# mippe_32u4.net
KiCad netlist of a schematic drawn in EAGLE
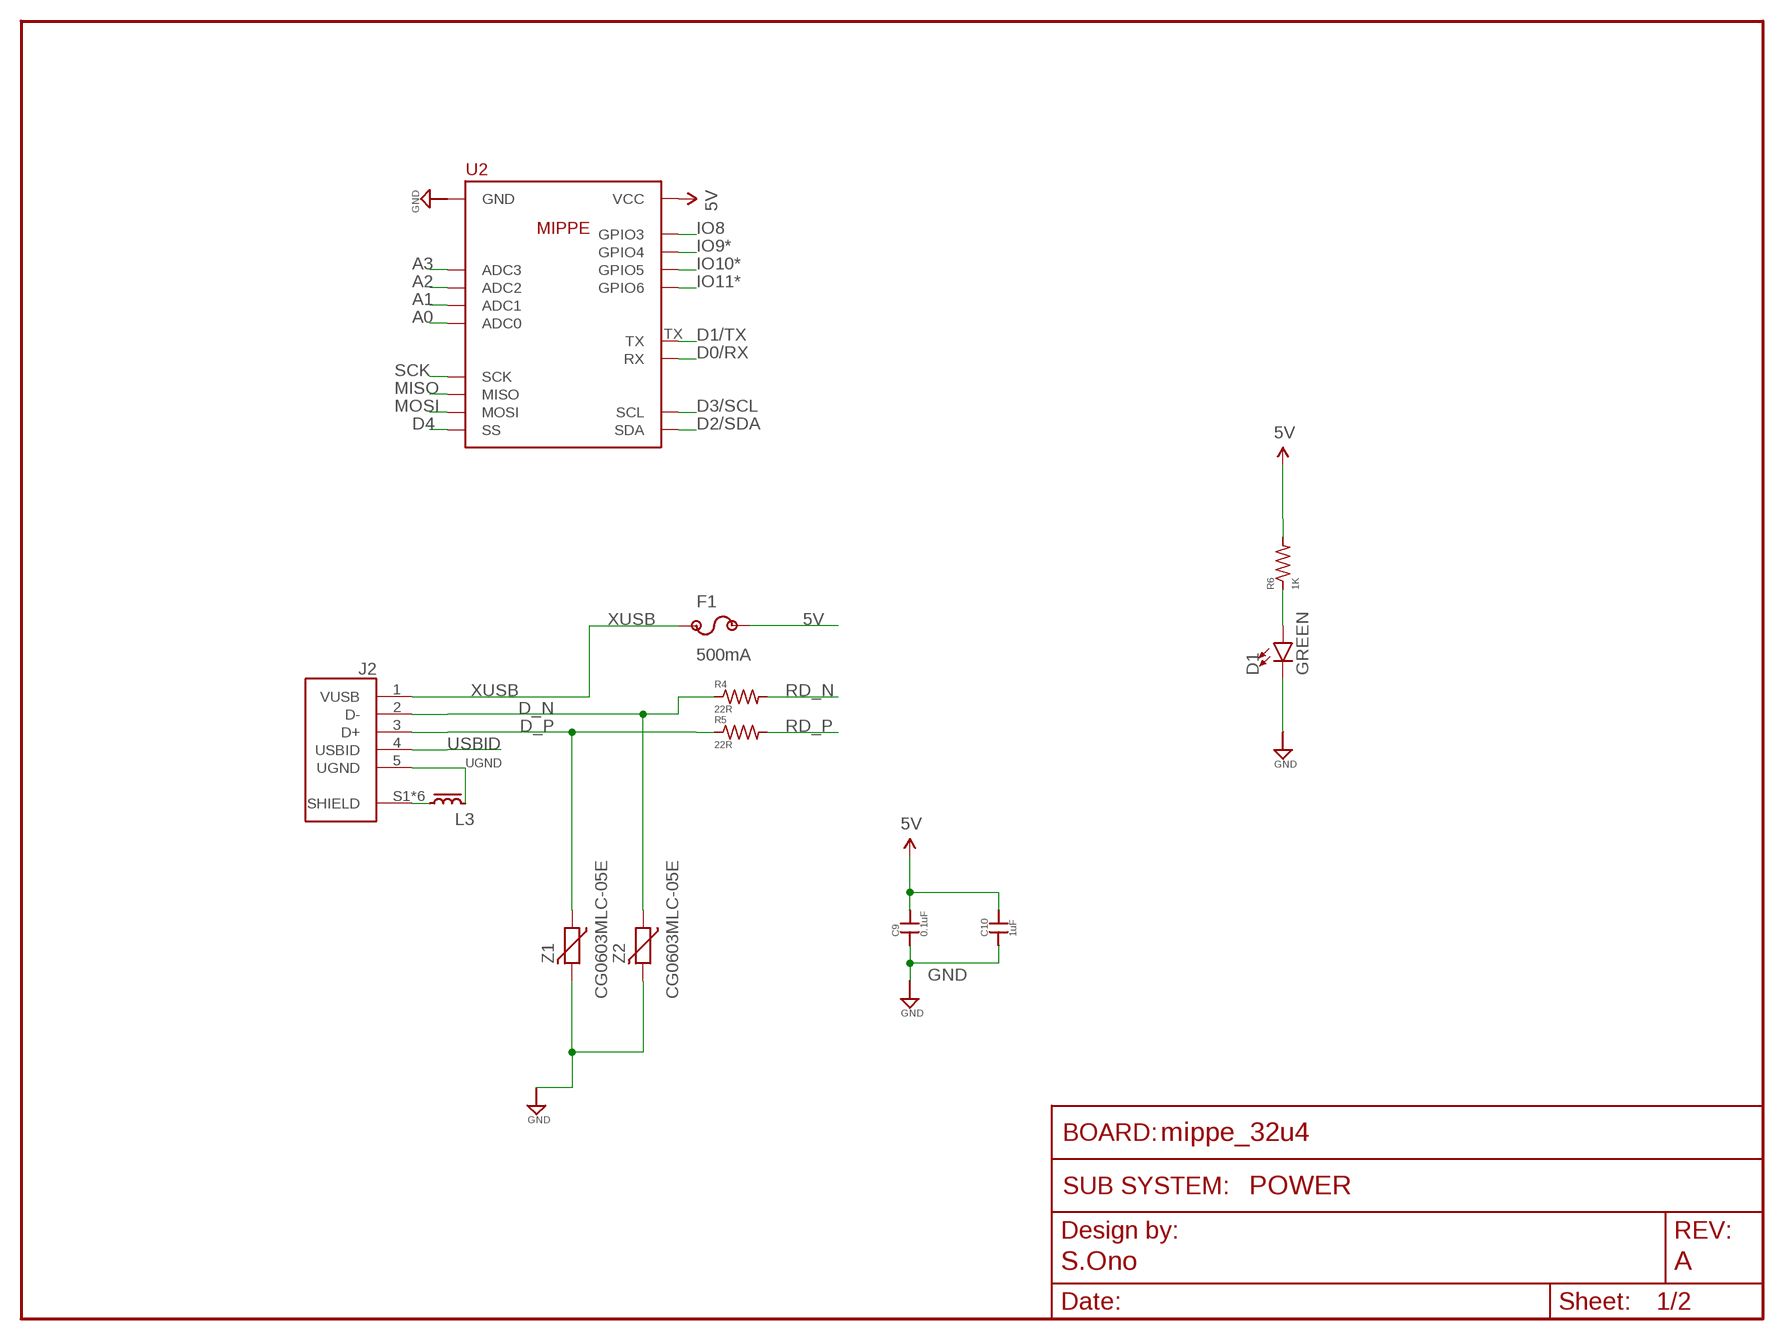
[diagram p0: schematic, sheet 1]
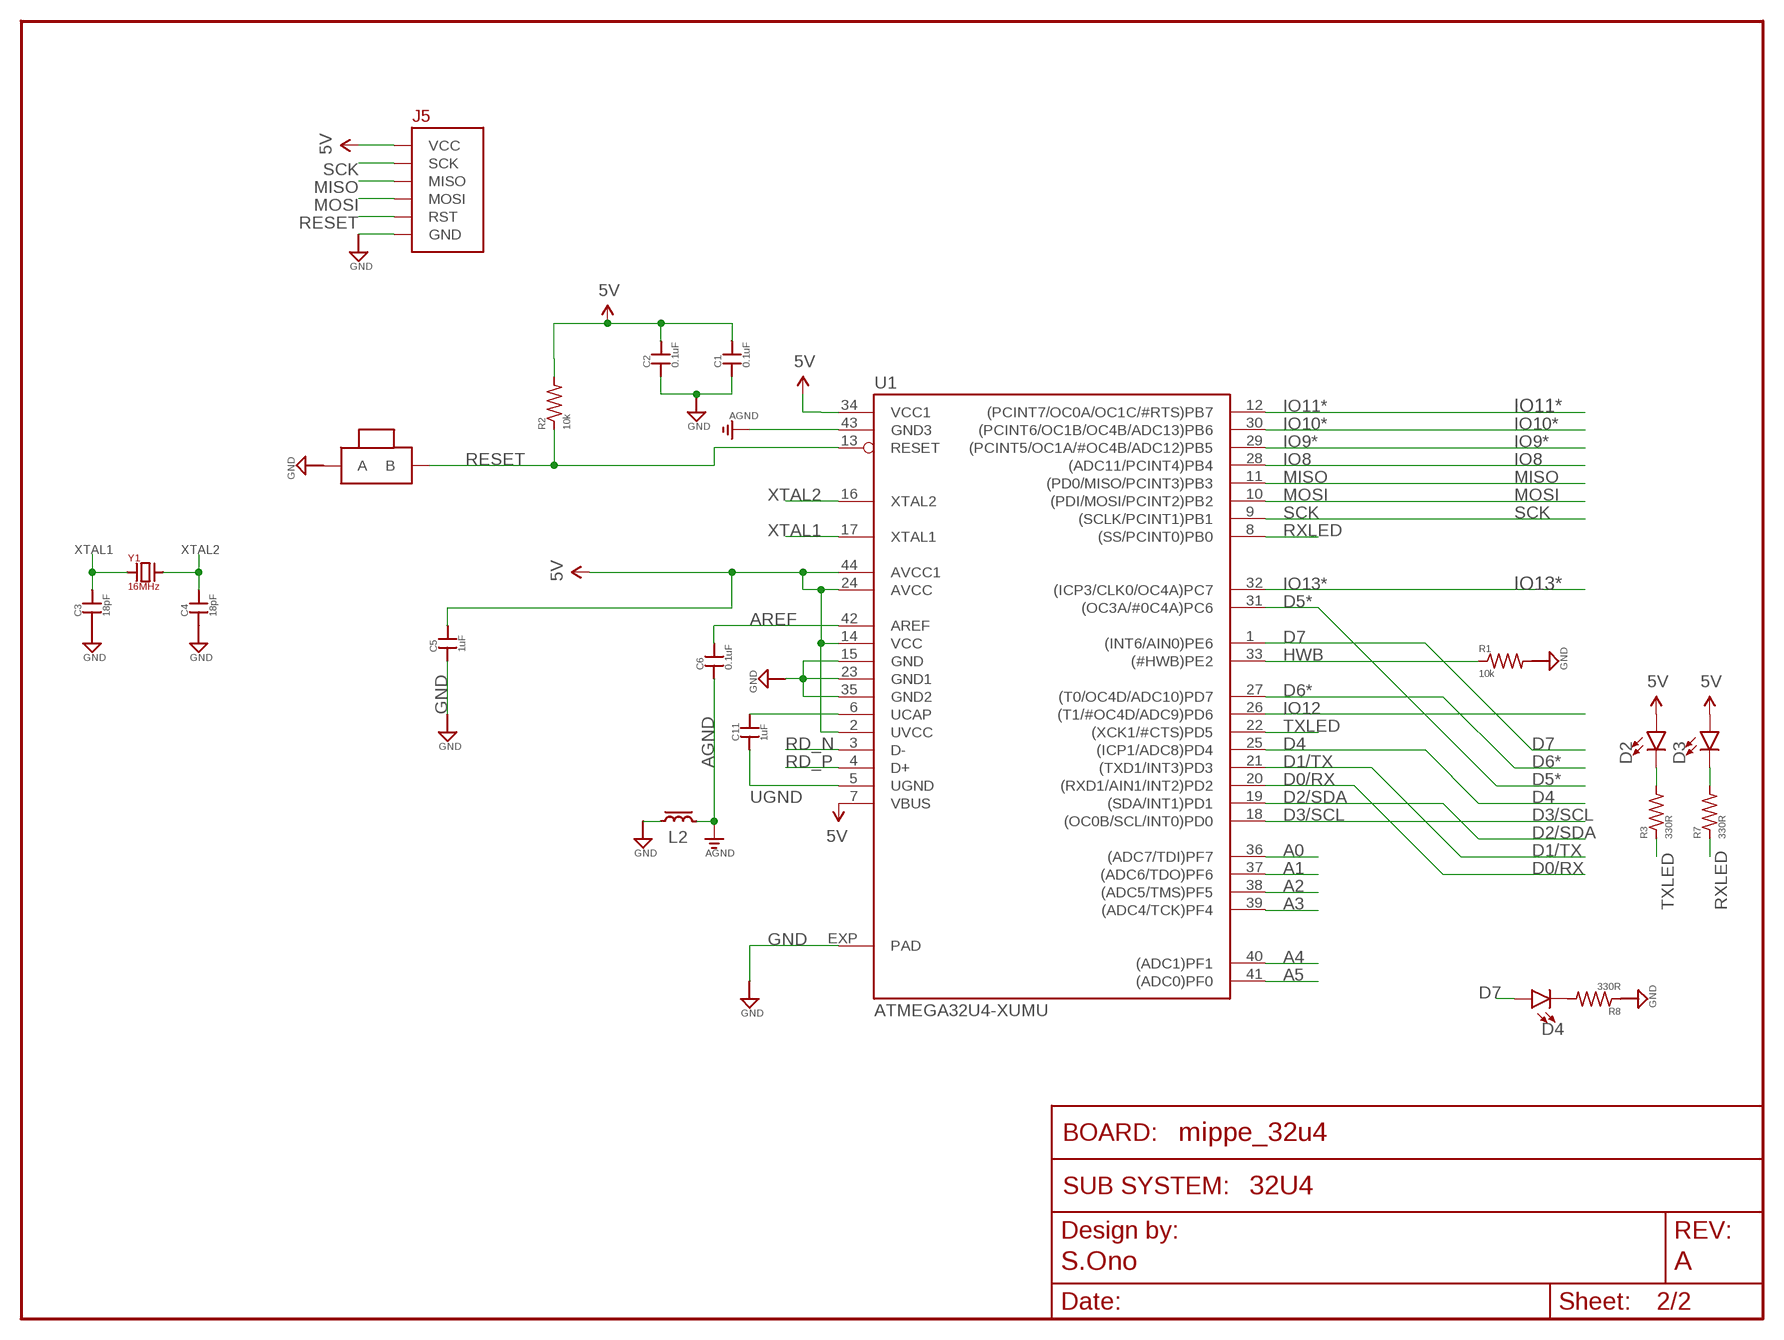
[diagram p1: schematic, sheet 2]

(export (version "E")
  (design (tool "Eeschema 10.0.6"))
  (components
    (comp (ref "C1")
      (value "0.1uF")
      (footprint "eagle-import:0603-CAP")
      (libsource (lib "eagle-import") (part "CAP0603-CAP"))
    )
    (comp (ref "C2")
      (value "0.1uF")
      (footprint "eagle-import:0603-CAP")
      (libsource (lib "eagle-import") (part "CAP0603-CAP"))
    )
    (comp (ref "C3")
      (value "18pF")
      (footprint "eagle-import:0603-CAP")
      (libsource (lib "eagle-import") (part "CAP0603-CAP"))
    )
    (comp (ref "C4")
      (value "18pF")
      (footprint "eagle-import:0603-CAP")
      (libsource (lib "eagle-import") (part "CAP0603-CAP"))
    )
    (comp (ref "C5")
      (value "1uF")
      (footprint "eagle-import:0603-CAP")
      (libsource (lib "eagle-import") (part "CAP0603-CAP"))
    )
    (comp (ref "C6")
      (value "0.1uF")
      (footprint "eagle-import:0603-CAP")
      (libsource (lib "eagle-import") (part "CAP0603-CAP"))
    )
    (comp (ref "C11")
      (value "1uF")
      (footprint "eagle-import:0603-CAP")
      (libsource (lib "eagle-import") (part "CAP0603-CAP"))
    )
    (comp (ref "D2")
      (value "LED0603")
      (footprint "eagle-import:LED-0603")
      (libsource (lib "eagle-import") (part "LED0603"))
    )
    (comp (ref "D3")
      (value "LED0603")
      (footprint "eagle-import:LED-0603")
      (libsource (lib "eagle-import") (part "LED0603"))
    )
    (comp (ref "D4")
      (value "LED0603")
      (footprint "eagle-import:LED-0603")
      (libsource (lib "eagle-import") (part "LED0603"))
    )
    (comp (ref "J5")
      (value "BURNIN")
      (footprint "eagle-import:BURNIN")
      (libsource (lib "eagle-import") (part "BURNIN"))
    )
    (comp (ref "L2")
      (value "IND")
      (footprint "eagle-import:IND_2012")
      (fields (field (name "MANUFACTURER_PART_NUMBER") "MLZ2012M1R0HT000"))
      (libsource (lib "eagle-import") (part "IND"))
    )
    (comp (ref "R1")
      (value "10k")
      (footprint "eagle-import:0603-RES")
      (libsource (lib "eagle-import") (part "R-US_0603"))
    )
    (comp (ref "R2")
      (value "10k")
      (footprint "eagle-import:0603-RES")
      (libsource (lib "eagle-import") (part "R-US_0603"))
    )
    (comp (ref "R3")
      (value "330R")
      (footprint "eagle-import:0603-RES")
      (libsource (lib "eagle-import") (part "R-US_0603"))
    )
    (comp (ref "R7")
      (value "330R")
      (footprint "eagle-import:0603-RES")
      (libsource (lib "eagle-import") (part "R-US_0603"))
    )
    (comp (ref "R8")
      (value "330R")
      (footprint "eagle-import:0603-RES")
      (libsource (lib "eagle-import") (part "R-US_0603"))
    )
    (comp (ref "SW1")
      (value "BTN-PTS810")
      (footprint "eagle-import:BTN_PTS810")
      (libsource (lib "eagle-import") (part "BTN-PTS810"))
    )
    (comp (ref "U1")
      (value "ATMEGA32U4-XUMU")
      (footprint "eagle-import:QFN44ML7X7")
      (libsource (lib "eagle-import") (part "ATMEGA32U4-XUMU"))
    )
    (comp (ref "Y1")
      (value "16MHz")
      (footprint "eagle-import:XTAL500X320X130N")
      (libsource (lib "eagle-import") (part "CRYSTAL_SMOL"))
    )
    (comp (ref "C9")
      (value "0.1uF")
      (footprint "eagle-import:0603-CAP")
      (libsource (lib "eagle-import") (part "CAP0603-CAP"))
    )
    (comp (ref "C10")
      (value "1uF")
      (footprint "eagle-import:0603-CAP")
      (libsource (lib "eagle-import") (part "CAP0603-CAP"))
    )
    (comp (ref "D1")
      (value "GREEN")
      (footprint "eagle-import:LED-0603")
      (libsource (lib "eagle-import") (part "LED0603"))
    )
    (comp (ref "F1")
      (value "500mA")
      (footprint "eagle-import:1206")
      (libsource (lib "eagle-import") (part "0ZCJ0050FF2G1206"))
    )
    (comp (ref "J2")
      (value "USB")
      (footprint "eagle-import:FCI_10103594-0001LF")
      (fields
        (field (name "DIGI-KEY_PART_NUMBER") "609-4050-1-ND")
        (field (name "MF") "Amphenol ICC")
        (field (name "MP") "10103594-0001LF")
      )
      (libsource (lib "eagle-import") (part "USB"))
    )
    (comp (ref "L3")
      (value "IND")
      (footprint "eagle-import:IND_2012")
      (fields (field (name "MANUFACTURER_PART_NUMBER") "MLZ2012M1R0HT000"))
      (libsource (lib "eagle-import") (part "IND"))
    )
    (comp (ref "R4")
      (value "22R")
      (footprint "eagle-import:0603-RES")
      (libsource (lib "eagle-import") (part "R-US_0603"))
    )
    (comp (ref "R5")
      (value "22R")
      (footprint "eagle-import:0603-RES")
      (libsource (lib "eagle-import") (part "R-US_0603"))
    )
    (comp (ref "R6")
      (value "1K")
      (footprint "eagle-import:0603-RES")
      (libsource (lib "eagle-import") (part "R-US_0603"))
    )
    (comp (ref "U2")
      (value "MIPPE")
      (footprint "eagle-import:MIPPE")
      (libsource (lib "eagle-import") (part "MIPPE"))
    )
    (comp (ref "Z1")
      (value "CG0603MLC-05E")
      (footprint "eagle-import:0603-RES")
      (libsource (lib "eagle-import") (part "VARISTOR"))
    )
    (comp (ref "Z2")
      (value "CG0603MLC-05E")
      (footprint "eagle-import:0603-RES")
      (libsource (lib "eagle-import") (part "VARISTOR"))
    )
  )
  (nets
    (net (code "1") (name "5V") (class "Default")
      (node (ref "C1") (pin "2") (pinfunction "2_2") (pintype "passive"))
      (node (ref "C10") (pin "2") (pinfunction "2_2") (pintype "passive"))
      (node (ref "C2") (pin "2") (pinfunction "2_2") (pintype "passive"))
      (node (ref "C5") (pin "2") (pinfunction "2_2") (pintype "passive"))
      (node (ref "C9") (pin "2") (pinfunction "2_2") (pintype "passive"))
      (node (ref "D2") (pin "A") (pinfunction "A_A") (pintype "passive"))
      (node (ref "D3") (pin "A") (pinfunction "A_A") (pintype "passive"))
      (node (ref "F1") (pin "2") (pinfunction "2_2") (pintype "passive"))
      (node (ref "J5") (pin "3.3V") (pinfunction "VCC_3.3V") (pintype "power_in"))
      (node (ref "R2") (pin "2") (pinfunction "2_2") (pintype "passive"))
      (node (ref "R6") (pin "2") (pinfunction "2_2") (pintype "passive"))
      (node (ref "U1") (pin "14") (pinfunction "VCC_14") (pintype "power_in"))
      (node (ref "U1") (pin "2") (pinfunction "UVCC_2") (pintype "power_in"))
      (node (ref "U1") (pin "24") (pinfunction "AVCC_24") (pintype "power_in"))
      (node (ref "U1") (pin "34") (pinfunction "VCC1_34") (pintype "power_in"))
      (node (ref "U1") (pin "44") (pinfunction "AVCC1_44") (pintype "power_in"))
      (node (ref "U1") (pin "7") (pinfunction "VBUS_7") (pintype "input"))
      (node (ref "U2") (pin "VCC") (pinfunction "VCC_VCC") (pintype "power_in"))
      (node (ref "U2") (pin "VCC@1") (pinfunction "VCC_VCC@1") (pintype "power_in"))
    )
    (net (code "2") (name "A0") (class "Default")
      (node (ref "U1") (pin "36") (pinfunction "(ADC7/TDI)PF7_36") (pintype "bidirectional"))
      (node (ref "U2") (pin "ADC0") (pinfunction "ADC0_ADC0") (pintype "bidirectional"))
    )
    (net (code "3") (name "A1") (class "Default")
      (node (ref "U1") (pin "37") (pinfunction "(ADC6/TDO)PF6_37") (pintype "bidirectional"))
      (node (ref "U2") (pin "ADC1") (pinfunction "ADC1_ADC1") (pintype "bidirectional"))
    )
    (net (code "4") (name "A2") (class "Default")
      (node (ref "U1") (pin "38") (pinfunction "(ADC5/TMS)PF5_38") (pintype "bidirectional"))
      (node (ref "U2") (pin "ADC2") (pinfunction "ADC2_ADC2") (pintype "bidirectional"))
    )
    (net (code "5") (name "A3") (class "Default")
      (node (ref "U1") (pin "39") (pinfunction "(ADC4/TCK)PF4_39") (pintype "bidirectional"))
      (node (ref "U2") (pin "ADC3") (pinfunction "ADC3_ADC3") (pintype "bidirectional"))
    )
    (net (code "6") (name "A4") (class "Default")
      (node (ref "U1") (pin "40") (pinfunction "(ADC1)PF1_40") (pintype "bidirectional"))
    )
    (net (code "7") (name "A5") (class "Default")
      (node (ref "U1") (pin "41") (pinfunction "(ADC0)PF0_41") (pintype "bidirectional"))
    )
    (net (code "8") (name "AGND") (class "Default")
      (node (ref "C6") (pin "1") (pinfunction "1_1") (pintype "passive"))
      (node (ref "L2") (pin "2") (pinfunction "P$2_2") (pintype "passive"))
      (node (ref "U1") (pin "43") (pinfunction "GND3_43") (pintype "power_in"))
    )
    (net (code "9") (name "AREF") (class "Default")
      (node (ref "C6") (pin "2") (pinfunction "2_2") (pintype "passive"))
      (node (ref "U1") (pin "42") (pinfunction "AREF_42") (pintype "power_in"))
    )
    (net (code "10") (name "D0{slash}RX") (class "Default")
      (node (ref "U1") (pin "20") (pinfunction "(RXD1/AIN1/INT2)PD2_20") (pintype "bidirectional"))
      (node (ref "U2") (pin "RX") (pinfunction "RX_RX") (pintype "bidirectional"))
    )
    (net (code "11") (name "D1{slash}TX") (class "Default")
      (node (ref "U1") (pin "21") (pinfunction "(TXD1/INT3)PD3_21") (pintype "bidirectional"))
      (node (ref "U2") (pin "TX") (pinfunction "TX_TX") (pintype "bidirectional"))
    )
    (net (code "12") (name "D2{slash}SDA") (class "Default")
      (node (ref "U1") (pin "19") (pinfunction "(SDA/INT1)PD1_19") (pintype "bidirectional"))
      (node (ref "U2") (pin "SDA") (pinfunction "SDA_SDA") (pintype "bidirectional"))
    )
    (net (code "13") (name "D3{slash}SCL") (class "Default")
      (node (ref "U1") (pin "18") (pinfunction "(OC0B/SCL/INT0)PD0_18") (pintype "bidirectional"))
      (node (ref "U2") (pin "SCL") (pinfunction "SCL_SCL") (pintype "bidirectional"))
    )
    (net (code "14") (name "D4") (class "Default")
      (node (ref "U1") (pin "25") (pinfunction "(ICP1/ADC8)PD4_25") (pintype "bidirectional"))
      (node (ref "U2") (pin "SS") (pinfunction "SS_SS") (pintype "bidirectional"))
    )
    (net (code "15") (name "D5*") (class "Default")
      (node (ref "U1") (pin "31") (pinfunction "(OC3A/#0C4A)PC6_31") (pintype "bidirectional"))
    )
    (net (code "16") (name "D6*") (class "Default")
      (node (ref "U1") (pin "27") (pinfunction "(T0/OC4D/ADC10)PD7_27") (pintype "bidirectional"))
    )
    (net (code "17") (name "D7") (class "Default")
      (node (ref "D4") (pin "A") (pinfunction "A_A") (pintype "passive"))
      (node (ref "U1") (pin "1") (pinfunction "(INT6/AIN0)PE6_1") (pintype "bidirectional"))
    )
    (net (code "18") (name "D_N") (class "Default")
      (node (ref "J2") (pin "2") (pinfunction "D-_2") (pintype "passive"))
      (node (ref "R4") (pin "1") (pinfunction "1_1") (pintype "passive"))
      (node (ref "Z2") (pin "1") (pinfunction "1_1") (pintype "passive"))
    )
    (net (code "19") (name "D_P") (class "Default")
      (node (ref "J2") (pin "3") (pinfunction "D+_3") (pintype "passive"))
      (node (ref "R5") (pin "1") (pinfunction "1_1") (pintype "passive"))
      (node (ref "Z1") (pin "1") (pinfunction "1_1") (pintype "passive"))
    )
    (net (code "20") (name "GND") (class "Default")
      (node (ref "C1") (pin "1") (pinfunction "1_1") (pintype "passive"))
      (node (ref "C10") (pin "1") (pinfunction "1_1") (pintype "passive"))
      (node (ref "C2") (pin "1") (pinfunction "1_1") (pintype "passive"))
      (node (ref "C3") (pin "1") (pinfunction "1_1") (pintype "passive"))
      (node (ref "C4") (pin "1") (pinfunction "1_1") (pintype "passive"))
      (node (ref "C5") (pin "1") (pinfunction "1_1") (pintype "passive"))
      (node (ref "C9") (pin "1") (pinfunction "1_1") (pintype "passive"))
      (node (ref "D1") (pin "C") (pinfunction "C_C") (pintype "passive"))
      (node (ref "J5") (pin "GND") (pinfunction "GND_GND") (pintype "power_in"))
      (node (ref "L2") (pin "1") (pinfunction "P$1_1") (pintype "passive"))
      (node (ref "R1") (pin "2") (pinfunction "2_2") (pintype "passive"))
      (node (ref "R8") (pin "1") (pinfunction "1_1") (pintype "passive"))
      (node (ref "SW1") (pin "1") (pinfunction "A_1") (pintype "bidirectional"))
      (node (ref "SW1") (pin "2") (pinfunction "A_2") (pintype "bidirectional"))
      (node (ref "U1") (pin "15") (pinfunction "GND_15") (pintype "power_in"))
      (node (ref "U1") (pin "23") (pinfunction "GND1_23") (pintype "power_in"))
      (node (ref "U1") (pin "35") (pinfunction "GND2_35") (pintype "power_in"))
      (node (ref "U1") (pin "EXP") (pinfunction "PAD_EXP") (pintype "power_in"))
      (node (ref "U2") (pin "GND@0") (pinfunction "GND_GND@0") (pintype "power_in"))
      (node (ref "U2") (pin "GND@1") (pinfunction "GND_GND@1") (pintype "power_in"))
      (node (ref "Z1") (pin "2") (pinfunction "2_2") (pintype "passive"))
      (node (ref "Z2") (pin "2") (pinfunction "2_2") (pintype "passive"))
    )
    (net (code "21") (name "HWB") (class "Default")
      (node (ref "R1") (pin "1") (pinfunction "1_1") (pintype "passive"))
      (node (ref "U1") (pin "33") (pinfunction "(#HWB)PE2_33") (pintype "bidirectional"))
    )
    (net (code "22") (name "IO8") (class "Default")
      (node (ref "U1") (pin "28") (pinfunction "(ADC11/PCINT4)PB4_28") (pintype "bidirectional"))
      (node (ref "U2") (pin "GPIO3") (pinfunction "GPIO3_GPIO3") (pintype "bidirectional"))
    )
    (net (code "23") (name "IO9*") (class "Default")
      (node (ref "U1") (pin "29") (pinfunction "(PCINT5/OC1A/#OC4B/ADC12)PB5_29") (pintype "bidirectional"))
      (node (ref "U2") (pin "GPIO4") (pinfunction "GPIO4_GPIO4") (pintype "bidirectional"))
    )
    (net (code "24") (name "IO10*") (class "Default")
      (node (ref "U1") (pin "30") (pinfunction "(PCINT6/OC1B/OC4B/ADC13)PB6_30") (pintype "bidirectional"))
      (node (ref "U2") (pin "GPIO5") (pinfunction "GPIO5_GPIO5") (pintype "bidirectional"))
    )
    (net (code "25") (name "IO11*") (class "Default")
      (node (ref "U1") (pin "12") (pinfunction "(PCINT7/OC0A/OC1C/#RTS)PB7_12") (pintype "bidirectional"))
      (node (ref "U2") (pin "GPIO6") (pinfunction "GPIO6_GPIO6") (pintype "bidirectional"))
    )
    (net (code "26") (name "IO12") (class "Default")
      (node (ref "U1") (pin "26") (pinfunction "(T1/#OC4D/ADC9)PD6_26") (pintype "bidirectional"))
    )
    (net (code "27") (name "IO13*") (class "Default")
      (node (ref "U1") (pin "32") (pinfunction "(ICP3/CLK0/OC4A)PC7_32") (pintype "bidirectional"))
    )
    (net (code "28") (name "MISO") (class "Default")
      (node (ref "J5") (pin "MISO") (pinfunction "MISO_MISO") (pintype "bidirectional"))
      (node (ref "U1") (pin "11") (pinfunction "(PD0/MISO/PCINT3)PB3_11") (pintype "bidirectional"))
      (node (ref "U2") (pin "MISO") (pinfunction "MISO_MISO") (pintype "bidirectional"))
    )
    (net (code "29") (name "MOSI") (class "Default")
      (node (ref "J5") (pin "MOSI") (pinfunction "MOSI_MOSI") (pintype "bidirectional"))
      (node (ref "U1") (pin "10") (pinfunction "(PDI/MOSI/PCINT2)PB2_10") (pintype "bidirectional"))
      (node (ref "U2") (pin "MOSI") (pinfunction "MOSI_MOSI") (pintype "bidirectional"))
    )
    (net (code "30") (name "Net-(D1-PadA)") (class "Default")
      (node (ref "D1") (pin "A") (pinfunction "A_A") (pintype "passive"))
      (node (ref "R6") (pin "1") (pinfunction "1_1") (pintype "passive"))
    )
    (net (code "31") (name "Net-(D2-PadC)") (class "Default")
      (node (ref "D2") (pin "C") (pinfunction "C_C") (pintype "passive"))
      (node (ref "R3") (pin "2") (pinfunction "2_2") (pintype "passive"))
    )
    (net (code "32") (name "Net-(D3-PadC)") (class "Default")
      (node (ref "D3") (pin "C") (pinfunction "C_C") (pintype "passive"))
      (node (ref "R7") (pin "2") (pinfunction "2_2") (pintype "passive"))
    )
    (net (code "33") (name "Net-(D4-PadC)") (class "Default")
      (node (ref "D4") (pin "C") (pinfunction "C_C") (pintype "passive"))
      (node (ref "R8") (pin "2") (pinfunction "2_2") (pintype "passive"))
    )
    (net (code "34") (name "Net-(L3-P$1)") (class "Default")
      (node (ref "J2") (pin "S1") (pinfunction "SHIELD_S1") (pintype "passive"))
      (node (ref "J2") (pin "S2") (pinfunction "SHIELD_S2") (pintype "passive"))
      (node (ref "J2") (pin "S3") (pinfunction "SHIELD_S3") (pintype "passive"))
      (node (ref "J2") (pin "S4") (pinfunction "SHIELD_S4") (pintype "passive"))
      (node (ref "J2") (pin "S5") (pinfunction "SHIELD_S5") (pintype "passive"))
      (node (ref "J2") (pin "S6") (pinfunction "SHIELD_S6") (pintype "passive"))
      (node (ref "L3") (pin "1") (pinfunction "P$1_1") (pintype "passive"))
    )
    (net (code "35") (name "Net-(U1-UCAP)") (class "Default")
      (node (ref "C11") (pin "2") (pinfunction "2_2") (pintype "passive"))
      (node (ref "U1") (pin "6") (pinfunction "UCAP_6") (pintype "passive"))
    )
    (net (code "36") (name "RD_N") (class "Default")
      (node (ref "R4") (pin "2") (pinfunction "2_2") (pintype "passive"))
      (node (ref "U1") (pin "3") (pinfunction "D-_3") (pintype "bidirectional"))
    )
    (net (code "37") (name "RD_P") (class "Default")
      (node (ref "R5") (pin "2") (pinfunction "2_2") (pintype "passive"))
      (node (ref "U1") (pin "4") (pinfunction "D+_4") (pintype "bidirectional"))
    )
    (net (code "38") (name "RESET") (class "Default")
      (node (ref "J5") (pin "RST") (pinfunction "RST_RST") (pintype "bidirectional"))
      (node (ref "R2") (pin "1") (pinfunction "1_1") (pintype "passive"))
      (node (ref "SW1") (pin "3") (pinfunction "B_3") (pintype "bidirectional"))
      (node (ref "SW1") (pin "4") (pinfunction "B_4") (pintype "bidirectional"))
      (node (ref "U1") (pin "13") (pinfunction "RESET_13") (pintype "input"))
    )
    (net (code "39") (name "RXLED") (class "Default")
      (node (ref "R7") (pin "1") (pinfunction "1_1") (pintype "passive"))
      (node (ref "U1") (pin "8") (pinfunction "(SS/PCINT0)PB0_8") (pintype "bidirectional"))
    )
    (net (code "40") (name "SCK") (class "Default")
      (node (ref "J5") (pin "SCK") (pinfunction "SCK_SCK") (pintype "bidirectional"))
      (node (ref "U1") (pin "9") (pinfunction "(SCLK/PCINT1)PB1_9") (pintype "bidirectional"))
      (node (ref "U2") (pin "SCK") (pinfunction "SCK_SCK") (pintype "bidirectional"))
    )
    (net (code "41") (name "TXLED") (class "Default")
      (node (ref "R3") (pin "1") (pinfunction "1_1") (pintype "passive"))
      (node (ref "U1") (pin "22") (pinfunction "(XCK1/#CTS)PD5_22") (pintype "bidirectional"))
    )
    (net (code "42") (name "UGND") (class "Default")
      (node (ref "C11") (pin "1") (pinfunction "1_1") (pintype "passive"))
      (node (ref "J2") (pin "5") (pinfunction "UGND_5") (pintype "passive"))
      (node (ref "L3") (pin "2") (pinfunction "P$2_2") (pintype "passive"))
      (node (ref "U1") (pin "5") (pinfunction "UGND_5") (pintype "power_in"))
    )
    (net (code "43") (name "USBID") (class "Default")
      (node (ref "J2") (pin "4") (pinfunction "USBID_4") (pintype "passive"))
    )
    (net (code "44") (name "XTAL1") (class "Default")
      (node (ref "C3") (pin "2") (pinfunction "2_2") (pintype "passive"))
      (node (ref "U1") (pin "17") (pinfunction "XTAL1_17") (pintype "bidirectional"))
      (node (ref "Y1") (pin "1") (pinfunction "A_1") (pintype "passive"))
    )
    (net (code "45") (name "XTAL2") (class "Default")
      (node (ref "C4") (pin "2") (pinfunction "2_2") (pintype "passive"))
      (node (ref "U1") (pin "16") (pinfunction "XTAL2_16") (pintype "bidirectional"))
      (node (ref "Y1") (pin "2") (pinfunction "B_2") (pintype "passive"))
    )
    (net (code "46") (name "XUSB") (class "Default")
      (node (ref "F1") (pin "1") (pinfunction "1_1") (pintype "passive"))
      (node (ref "J2") (pin "1") (pinfunction "VUSB_1") (pintype "passive"))
    )
  )
)
